# kitco5.net
KiCad netlist of a schematic drawn in EAGLE
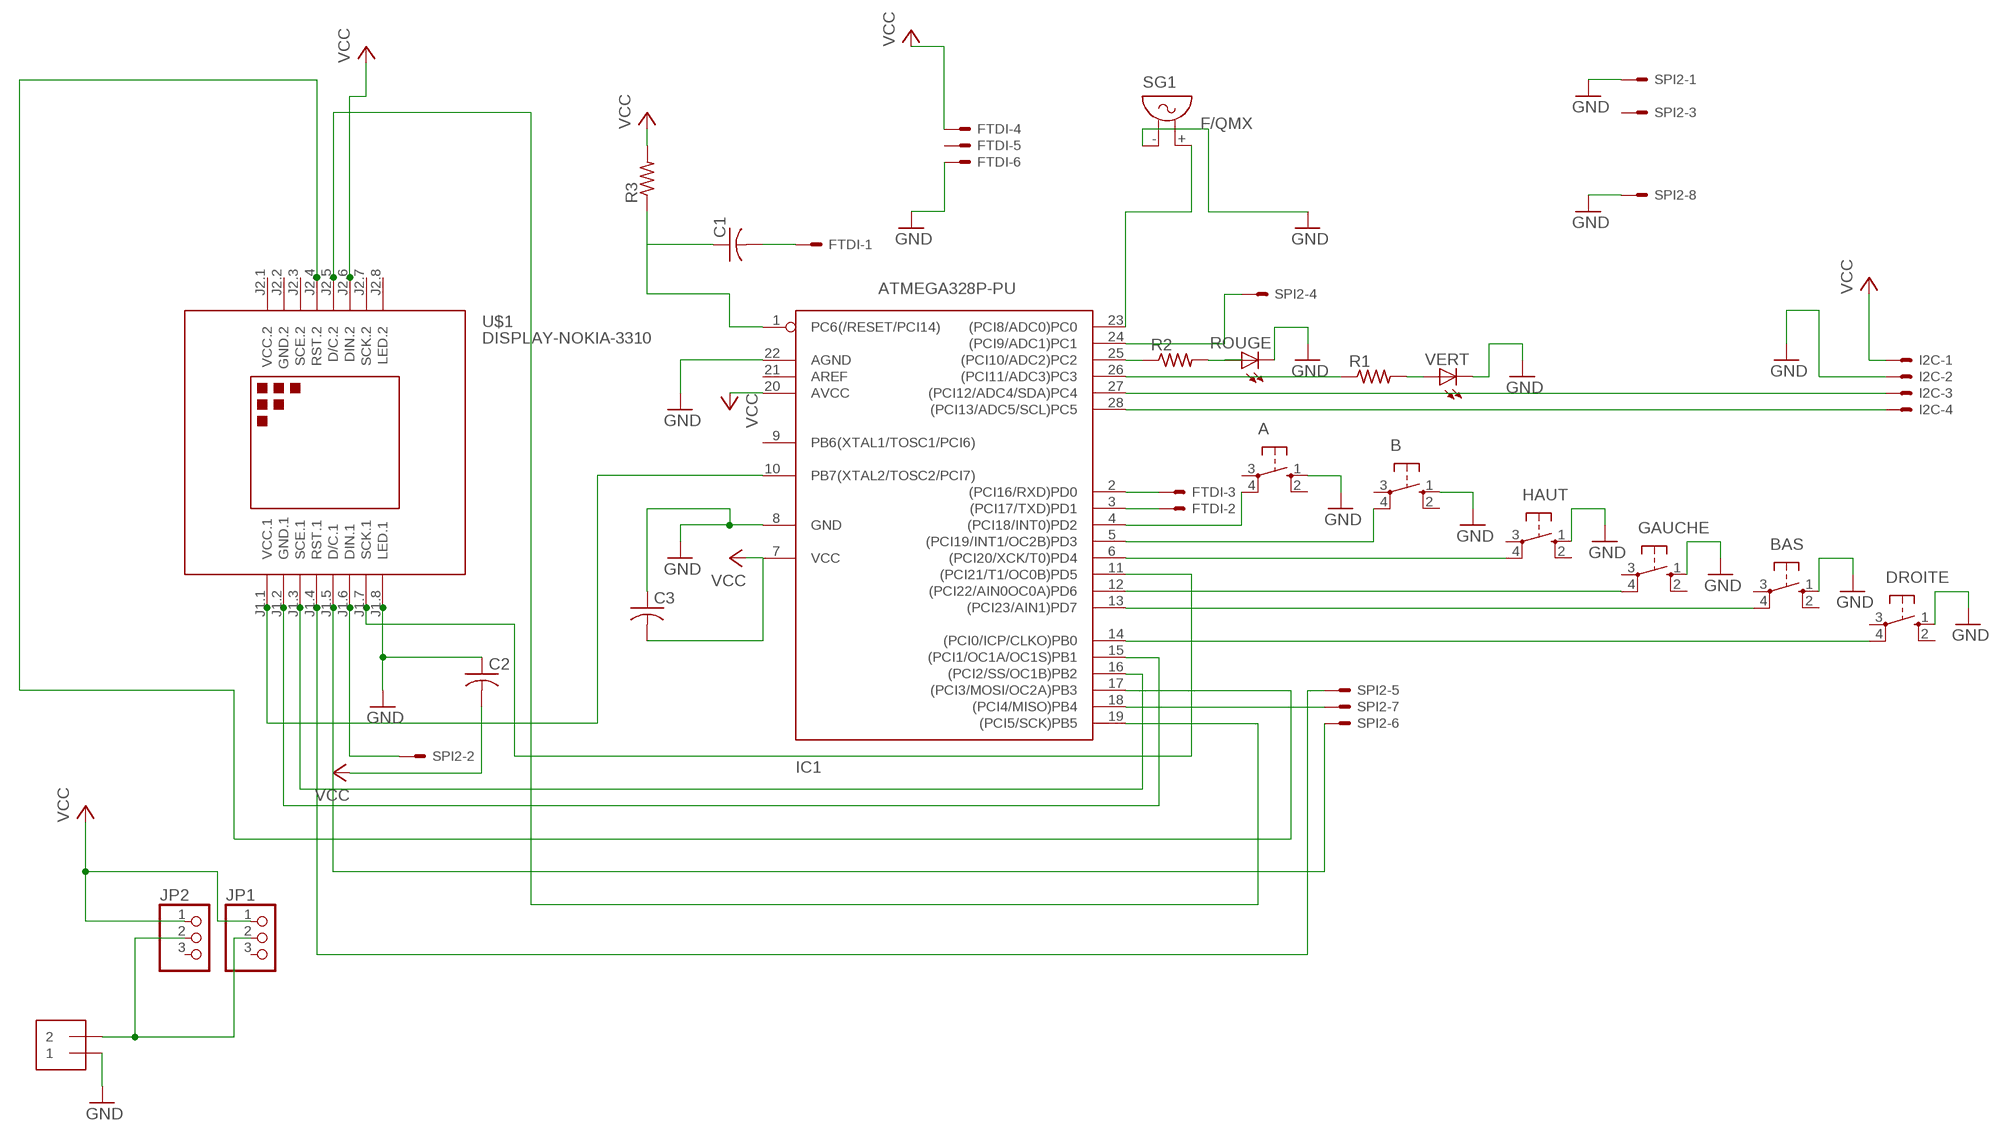
[diagram p0: schematic, sheet 1]

(export (version "E")
  (design (tool "Eeschema 10.0.6"))
  (components
    (comp (ref "A")
      (value "10-XX")
      (footprint "eagle-import:B3F-10XX")
      (fields (field (name "MPN") "B3F-1000"))
      (libsource (lib "eagle-import") (part "10-XX"))
    )
    (comp (ref "B")
      (value "10-XX")
      (footprint "eagle-import:B3F-10XX")
      (fields (field (name "MPN") "B3F-1000"))
      (libsource (lib "eagle-import") (part "10-XX"))
    )
    (comp (ref "BAS")
      (value "10-XX")
      (footprint "eagle-import:B3F-10XX")
      (fields (field (name "MPN") "B3F-1000"))
      (libsource (lib "eagle-import") (part "10-XX"))
    )
    (comp (ref "C1")
      (value "C-US025-040X050")
      (footprint "eagle-import:C025-040X050")
      (libsource (lib "eagle-import") (part "C-US025-040X050"))
    )
    (comp (ref "C2")
      (value "C-US025-040X050")
      (footprint "eagle-import:C025-040X050")
      (libsource (lib "eagle-import") (part "C-US025-040X050"))
    )
    (comp (ref "C3")
      (value "C-US025-040X050")
      (footprint "eagle-import:C025-040X050")
      (libsource (lib "eagle-import") (part "C-US025-040X050"))
    )
    (comp (ref "DROITE")
      (value "10-XX")
      (footprint "eagle-import:B3F-10XX")
      (fields (field (name "MPN") "B3F-1000"))
      (libsource (lib "eagle-import") (part "10-XX"))
    )
    (comp (ref "FTDI")
      (value "22-23-2061")
      (footprint "eagle-import:22-23-2061")
      (fields (field (name "MF") "MOLEX"))
      (libsource (lib "eagle-import") (part "22-23-2061"))
    )
    (comp (ref "GAUCHE")
      (value "10-XX")
      (footprint "eagle-import:B3F-10XX")
      (fields (field (name "MPN") "B3F-1000"))
      (libsource (lib "eagle-import") (part "10-XX"))
    )
    (comp (ref "HAUT")
      (value "10-XX")
      (footprint "eagle-import:B3F-10XX")
      (fields (field (name "MPN") "B3F-1000"))
      (libsource (lib "eagle-import") (part "10-XX"))
    )
    (comp (ref "I2C")
      (value "22-23-2041")
      (footprint "eagle-import:22-23-2041")
      (fields (field (name "MF") "MOLEX"))
      (libsource (lib "eagle-import") (part "22-23-2041"))
    )
    (comp (ref "IC1")
      (value "ATMEGA328P-PU")
      (footprint "eagle-import:DIL28-3")
      (libsource (lib "eagle-import") (part "ATMEGA168PV-10"))
    )
    (comp (ref "J1")
      (value "1X2-3.5MM")
      (footprint "eagle-import:1X2-3.5MM")
      (libsource (lib "eagle-import") (part "1X2-3.5MM"))
    )
    (comp (ref "JP1")
      (value "PINHD-1X3")
      (footprint "eagle-import:1X03")
      (libsource (lib "eagle-import") (part "PINHD-1X3"))
    )
    (comp (ref "JP2")
      (value "PINHD-1X3")
      (footprint "eagle-import:1X03")
      (libsource (lib "eagle-import") (part "PINHD-1X3"))
    )
    (comp (ref "R1")
      (value "R-US_0207/10")
      (footprint "eagle-import:0207_10")
      (libsource (lib "eagle-import") (part "R-US_0207/10"))
    )
    (comp (ref "R2")
      (value "R-US_0207/10")
      (footprint "eagle-import:0207_10")
      (libsource (lib "eagle-import") (part "R-US_0207/10"))
    )
    (comp (ref "R3")
      (value "R-US_0207/10")
      (footprint "eagle-import:0207_10")
      (libsource (lib "eagle-import") (part "R-US_0207/10"))
    )
    (comp (ref "ROUGE")
      (value "LED5MM")
      (footprint "eagle-import:LED5MM")
      (libsource (lib "eagle-import") (part "LED5MM"))
    )
    (comp (ref "SG1")
      (value "F/QMX")
      (footprint "eagle-import:F_QMX")
      (libsource (lib "eagle-import") (part "F/QMX"))
    )
    (comp (ref "SPI2")
      (value "22-23-2081")
      (footprint "eagle-import:22-23-2081")
      (fields (field (name "MF") "MOLEX"))
      (libsource (lib "eagle-import") (part "22-23-2081"))
    )
    (comp (ref "U$1")
      (value "DISPLAY-NOKIA-3310")
      (footprint "eagle-import:DISPLAY-NOKIA-3310")
      (libsource (lib "eagle-import") (part "DISPLAY-NOKIA-3310"))
    )
    (comp (ref "VERT")
      (value "LED5MM")
      (footprint "eagle-import:LED5MM")
      (libsource (lib "eagle-import") (part "LED5MM"))
    )
  )
  (nets
    (net (code "1") (name "/GND.2") (class "Default")
      (node (ref "U$1") (pin "J2.2") (pinfunction "GND.2_J2.2") (pintype "power_in"))
    )
    (net (code "2") (name "/VCC.2") (class "Default")
      (node (ref "U$1") (pin "J2.1") (pinfunction "VCC.2_J2.1") (pintype "power_in"))
    )
    (net (code "3") (name "GND") (class "Default")
      (node (ref "A") (pin "1") (pinfunction "S_1") (pintype "passive"))
      (node (ref "B") (pin "1") (pinfunction "S_1") (pintype "passive"))
      (node (ref "BAS") (pin "1") (pinfunction "S_1") (pintype "passive"))
      (node (ref "C2") (pin "1") (pinfunction "1_1") (pintype "passive"))
      (node (ref "C3") (pin "1") (pinfunction "1_1") (pintype "passive"))
      (node (ref "DROITE") (pin "1") (pinfunction "S_1") (pintype "passive"))
      (node (ref "FTDI") (pin "6") (pinfunction "S_6") (pintype "passive"))
      (node (ref "GAUCHE") (pin "1") (pinfunction "S_1") (pintype "passive"))
      (node (ref "HAUT") (pin "1") (pinfunction "S_1") (pintype "passive"))
      (node (ref "I2C") (pin "2") (pinfunction "S_2") (pintype "passive"))
      (node (ref "IC1") (pin "22") (pinfunction "AGND_22") (pintype "bidirectional"))
      (node (ref "IC1") (pin "8") (pinfunction "GND_8") (pintype "bidirectional"))
      (node (ref "J1") (pin "1") (pinfunction "1_1") (pintype "passive"))
      (node (ref "ROUGE") (pin "K") (pinfunction "C_K") (pintype "passive"))
      (node (ref "SG1") (pin "-") (pinfunction "1_-") (pintype "passive"))
      (node (ref "SPI2") (pin "1") (pinfunction "S_1") (pintype "passive"))
      (node (ref "SPI2") (pin "8") (pinfunction "S_8") (pintype "passive"))
      (node (ref "U$1") (pin "J1.8") (pinfunction "LED.1_J1.8") (pintype "input"))
      (node (ref "VERT") (pin "K") (pinfunction "C_K") (pintype "passive"))
    )
    (net (code "4") (name "Net-(A-P1)") (class "Default")
      (node (ref "A") (pin "4") (pinfunction "P1_4") (pintype "passive"))
      (node (ref "IC1") (pin "4") (pinfunction "(PCI18/INT0)PD2_4") (pintype "bidirectional"))
    )
    (net (code "5") (name "Net-(B-P1)") (class "Default")
      (node (ref "B") (pin "4") (pinfunction "P1_4") (pintype "passive"))
      (node (ref "IC1") (pin "5") (pinfunction "(PCI19/INT1/OC2B)PD3_5") (pintype "bidirectional"))
    )
    (net (code "6") (name "Net-(BAS-P1)") (class "Default")
      (node (ref "BAS") (pin "4") (pinfunction "P1_4") (pintype "passive"))
      (node (ref "IC1") (pin "13") (pinfunction "(PCI23/AIN1)PD7_13") (pintype "bidirectional"))
    )
    (net (code "7") (name "Net-(DROITE-P1)") (class "Default")
      (node (ref "DROITE") (pin "4") (pinfunction "P1_4") (pintype "passive"))
      (node (ref "IC1") (pin "14") (pinfunction "(PCI0/ICP/CLKO)PB0_14") (pintype "bidirectional"))
    )
    (net (code "8") (name "Net-(FTDIA-S)") (class "Default")
      (node (ref "C1") (pin "2") (pinfunction "2_2") (pintype "passive"))
      (node (ref "FTDI") (pin "1") (pinfunction "S_1") (pintype "passive"))
    )
    (net (code "9") (name "Net-(FTDIB-S)") (class "Default")
      (node (ref "FTDI") (pin "2") (pinfunction "S_2") (pintype "passive"))
      (node (ref "IC1") (pin "3") (pinfunction "(PCI17/TXD)PD1_3") (pintype "bidirectional"))
    )
    (net (code "10") (name "Net-(FTDIC-S)") (class "Default")
      (node (ref "FTDI") (pin "3") (pinfunction "S_3") (pintype "passive"))
      (node (ref "IC1") (pin "2") (pinfunction "(PCI16/RXD)PD0_2") (pintype "bidirectional"))
    )
    (net (code "11") (name "Net-(GAUCHE-P1)") (class "Default")
      (node (ref "GAUCHE") (pin "4") (pinfunction "P1_4") (pintype "passive"))
      (node (ref "IC1") (pin "12") (pinfunction "(PCI22/AIN0OC0A)PD6_12") (pintype "bidirectional"))
    )
    (net (code "12") (name "Net-(HAUT-P1)") (class "Default")
      (node (ref "HAUT") (pin "4") (pinfunction "P1_4") (pintype "passive"))
      (node (ref "IC1") (pin "6") (pinfunction "(PCI20/XCK/T0)PD4_6") (pintype "bidirectional"))
    )
    (net (code "13") (name "Net-(I2CC-S)") (class "Default")
      (node (ref "I2C") (pin "3") (pinfunction "S_3") (pintype "passive"))
      (node (ref "IC1") (pin "27") (pinfunction "(PCI12/ADC4/SDA)PC4_27") (pintype "bidirectional"))
    )
    (net (code "14") (name "Net-(I2CD-S)") (class "Default")
      (node (ref "I2C") (pin "4") (pinfunction "S_4") (pintype "passive"))
      (node (ref "IC1") (pin "28") (pinfunction "(PCI13/ADC5/SCL)PC5_28") (pintype "bidirectional"))
    )
    (net (code "15") (name "Net-(IC1-(PCI1{slash}OC1A{slash}OC1S)PB1)") (class "Default")
      (node (ref "IC1") (pin "15") (pinfunction "(PCI1/OC1A/OC1S)PB1_15") (pintype "bidirectional"))
      (node (ref "U$1") (pin "J1.2") (pinfunction "GND.1_J1.2") (pintype "power_in"))
    )
    (net (code "16") (name "Net-(IC1-(PCI2{slash}SS{slash}OC1B)PB2)") (class "Default")
      (node (ref "IC1") (pin "16") (pinfunction "(PCI2/SS/OC1B)PB2_16") (pintype "bidirectional"))
      (node (ref "U$1") (pin "J1.3") (pinfunction "SCE.1_J1.3") (pintype "bidirectional"))
    )
    (net (code "17") (name "Net-(IC1-(PCI3{slash}MOSI{slash}OC2A)PB3)") (class "Default")
      (node (ref "IC1") (pin "17") (pinfunction "(PCI3/MOSI/OC2A)PB3_17") (pintype "bidirectional"))
      (node (ref "U$1") (pin "J2.4") (pinfunction "RST.2_J2.4") (pintype "bidirectional"))
    )
    (net (code "18") (name "Net-(IC1-(PCI4{slash}MISO)PB4)") (class "Default")
      (node (ref "IC1") (pin "18") (pinfunction "(PCI4/MISO)PB4_18") (pintype "bidirectional"))
      (node (ref "SPI2") (pin "7") (pinfunction "S_7") (pintype "passive"))
    )
    (net (code "19") (name "Net-(IC1-(PCI5{slash}SCK)PB5)") (class "Default")
      (node (ref "IC1") (pin "19") (pinfunction "(PCI5/SCK)PB5_19") (pintype "bidirectional"))
      (node (ref "U$1") (pin "J2.5") (pinfunction "D/C.2_J2.5") (pintype "bidirectional"))
    )
    (net (code "20") (name "Net-(IC1-(PCI8{slash}ADC0)PC0)") (class "Default")
      (node (ref "IC1") (pin "23") (pinfunction "(PCI8/ADC0)PC0_23") (pintype "bidirectional"))
      (node (ref "SG1") (pin "+") (pinfunction "2_+") (pintype "passive"))
    )
    (net (code "21") (name "Net-(IC1-(PCI9{slash}ADC1)PC1)") (class "Default")
      (node (ref "IC1") (pin "24") (pinfunction "(PCI9/ADC1)PC1_24") (pintype "bidirectional"))
      (node (ref "SPI2") (pin "4") (pinfunction "S_4") (pintype "passive"))
    )
    (net (code "22") (name "Net-(IC1-(PCI10{slash}ADC2)PC2)") (class "Default")
      (node (ref "IC1") (pin "25") (pinfunction "(PCI10/ADC2)PC2_25") (pintype "bidirectional"))
      (node (ref "R2") (pin "1") (pinfunction "1_1") (pintype "passive"))
    )
    (net (code "23") (name "Net-(IC1-(PCI11{slash}ADC3)PC3)") (class "Default")
      (node (ref "IC1") (pin "26") (pinfunction "(PCI11/ADC3)PC3_26") (pintype "bidirectional"))
      (node (ref "R1") (pin "1") (pinfunction "1_1") (pintype "passive"))
    )
    (net (code "24") (name "Net-(IC1-(PCI21{slash}T1{slash}OC0B)PD5)") (class "Default")
      (node (ref "IC1") (pin "11") (pinfunction "(PCI21/T1/OC0B)PD5_11") (pintype "bidirectional"))
      (node (ref "U$1") (pin "J1.7") (pinfunction "SCK.1_J1.7") (pintype "bidirectional"))
    )
    (net (code "25") (name "Net-(IC1-PB7(XTAL2{slash}TOSC2{slash}PCI7))") (class "Default")
      (node (ref "IC1") (pin "10") (pinfunction "PB7(XTAL2/TOSC2/PCI7)_10") (pintype "bidirectional"))
      (node (ref "U$1") (pin "J1.1") (pinfunction "VCC.1_J1.1") (pintype "power_in"))
    )
    (net (code "26") (name "Net-(IC1-PC6({slash}RESET{slash}PCI14))") (class "Default")
      (node (ref "C1") (pin "1") (pinfunction "1_1") (pintype "passive"))
      (node (ref "IC1") (pin "1") (pinfunction "PC6(/RESET/PCI14)_1") (pintype "bidirectional"))
      (node (ref "R3") (pin "1") (pinfunction "1_1") (pintype "passive"))
    )
    (net (code "27") (name "Net-(J1-Pad2)") (class "Default")
      (node (ref "J1") (pin "2") (pinfunction "2_2") (pintype "passive"))
      (node (ref "JP1") (pin "2") (pinfunction "2_2") (pintype "passive"))
      (node (ref "JP2") (pin "2") (pinfunction "2_2") (pintype "passive"))
    )
    (net (code "28") (name "Net-(R1-Pad2)") (class "Default")
      (node (ref "R1") (pin "2") (pinfunction "2_2") (pintype "passive"))
      (node (ref "VERT") (pin "A") (pinfunction "A_A") (pintype "passive"))
    )
    (net (code "29") (name "Net-(R2-Pad2)") (class "Default")
      (node (ref "R2") (pin "2") (pinfunction "2_2") (pintype "passive"))
      (node (ref "ROUGE") (pin "A") (pinfunction "A_A") (pintype "passive"))
    )
    (net (code "30") (name "Net-(SPI2B-S)") (class "Default")
      (node (ref "SPI2") (pin "2") (pinfunction "S_2") (pintype "passive"))
      (node (ref "U$1") (pin "J1.6") (pinfunction "DIN.1_J1.6") (pintype "bidirectional"))
    )
    (net (code "31") (name "Net-(SPI2E-S)") (class "Default")
      (node (ref "SPI2") (pin "5") (pinfunction "S_5") (pintype "passive"))
      (node (ref "U$1") (pin "J1.4") (pinfunction "RST.1_J1.4") (pintype "bidirectional"))
    )
    (net (code "32") (name "Net-(SPI2F-S)") (class "Default")
      (node (ref "SPI2") (pin "6") (pinfunction "S_6") (pintype "passive"))
      (node (ref "U$1") (pin "J1.5") (pinfunction "D/C.1_J1.5") (pintype "bidirectional"))
    )
    (net (code "33") (name "VCC") (class "Default")
      (node (ref "C2") (pin "2") (pinfunction "2_2") (pintype "passive"))
      (node (ref "C3") (pin "2") (pinfunction "2_2") (pintype "passive"))
      (node (ref "FTDI") (pin "4") (pinfunction "S_4") (pintype "passive"))
      (node (ref "I2C") (pin "1") (pinfunction "S_1") (pintype "passive"))
      (node (ref "IC1") (pin "20") (pinfunction "AVCC_20") (pintype "bidirectional"))
      (node (ref "IC1") (pin "7") (pinfunction "VCC_7") (pintype "bidirectional"))
      (node (ref "JP1") (pin "1") (pinfunction "1_1") (pintype "passive"))
      (node (ref "JP2") (pin "1") (pinfunction "1_1") (pintype "passive"))
      (node (ref "R3") (pin "2") (pinfunction "2_2") (pintype "passive"))
      (node (ref "U$1") (pin "J2.6") (pinfunction "DIN.2_J2.6") (pintype "bidirectional"))
    )
    (net (code "34") (name "unconnected-(A-P-Pad3)") (class "Default")
      (node (ref "A") (pin "3") (pinfunction "P_3") (pintype "passive"))
    )
    (net (code "35") (name "unconnected-(A-S1-Pad2)") (class "Default")
      (node (ref "A") (pin "2") (pinfunction "S1_2") (pintype "passive"))
    )
    (net (code "36") (name "unconnected-(B-P-Pad3)") (class "Default")
      (node (ref "B") (pin "3") (pinfunction "P_3") (pintype "passive"))
    )
    (net (code "37") (name "unconnected-(B-S1-Pad2)") (class "Default")
      (node (ref "B") (pin "2") (pinfunction "S1_2") (pintype "passive"))
    )
    (net (code "38") (name "unconnected-(BAS-P-Pad3)") (class "Default")
      (node (ref "BAS") (pin "3") (pinfunction "P_3") (pintype "passive"))
    )
    (net (code "39") (name "unconnected-(BAS-S1-Pad2)") (class "Default")
      (node (ref "BAS") (pin "2") (pinfunction "S1_2") (pintype "passive"))
    )
    (net (code "40") (name "unconnected-(DROITE-P-Pad3)") (class "Default")
      (node (ref "DROITE") (pin "3") (pinfunction "P_3") (pintype "passive"))
    )
    (net (code "41") (name "unconnected-(DROITE-S1-Pad2)") (class "Default")
      (node (ref "DROITE") (pin "2") (pinfunction "S1_2") (pintype "passive"))
    )
    (net (code "42") (name "unconnected-(FTDIE-S-Pad5)") (class "Default")
      (node (ref "FTDI") (pin "5") (pinfunction "S_5") (pintype "passive"))
    )
    (net (code "43") (name "unconnected-(GAUCHE-P-Pad3)") (class "Default")
      (node (ref "GAUCHE") (pin "3") (pinfunction "P_3") (pintype "passive"))
    )
    (net (code "44") (name "unconnected-(GAUCHE-S1-Pad2)") (class "Default")
      (node (ref "GAUCHE") (pin "2") (pinfunction "S1_2") (pintype "passive"))
    )
    (net (code "45") (name "unconnected-(HAUT-P-Pad3)") (class "Default")
      (node (ref "HAUT") (pin "3") (pinfunction "P_3") (pintype "passive"))
    )
    (net (code "46") (name "unconnected-(HAUT-S1-Pad2)") (class "Default")
      (node (ref "HAUT") (pin "2") (pinfunction "S1_2") (pintype "passive"))
    )
    (net (code "47") (name "unconnected-(IC1-AREF-Pad21)") (class "Default")
      (node (ref "IC1") (pin "21") (pinfunction "AREF_21") (pintype "bidirectional"))
    )
    (net (code "48") (name "unconnected-(IC1-PB6(XTAL1{slash}TOSC1{slash}PCI6)-Pad9)") (class "Default")
      (node (ref "IC1") (pin "9") (pinfunction "PB6(XTAL1/TOSC1/PCI6)_9") (pintype "bidirectional"))
    )
    (net (code "49") (name "unconnected-(JP1-Pad3)") (class "Default")
      (node (ref "JP1") (pin "3") (pinfunction "3_3") (pintype "passive"))
    )
    (net (code "50") (name "unconnected-(JP2-Pad3)") (class "Default")
      (node (ref "JP2") (pin "3") (pinfunction "3_3") (pintype "passive"))
    )
    (net (code "51") (name "unconnected-(SPI2C-S-Pad3)") (class "Default")
      (node (ref "SPI2") (pin "3") (pinfunction "S_3") (pintype "passive"))
    )
    (net (code "52") (name "unconnected-(U$1-LED.2-PadJ2.8)") (class "Default")
      (node (ref "U$1") (pin "J2.8") (pinfunction "LED.2_J2.8") (pintype "input"))
    )
    (net (code "53") (name "unconnected-(U$1-SCE.2-PadJ2.3)") (class "Default")
      (node (ref "U$1") (pin "J2.3") (pinfunction "SCE.2_J2.3") (pintype "bidirectional"))
    )
    (net (code "54") (name "unconnected-(U$1-SCK.2-PadJ2.7)") (class "Default")
      (node (ref "U$1") (pin "J2.7") (pinfunction "SCK.2_J2.7") (pintype "bidirectional"))
    )
  )
)
